# mixer.net
KiCad netlist of a schematic drawn in Altium Designer
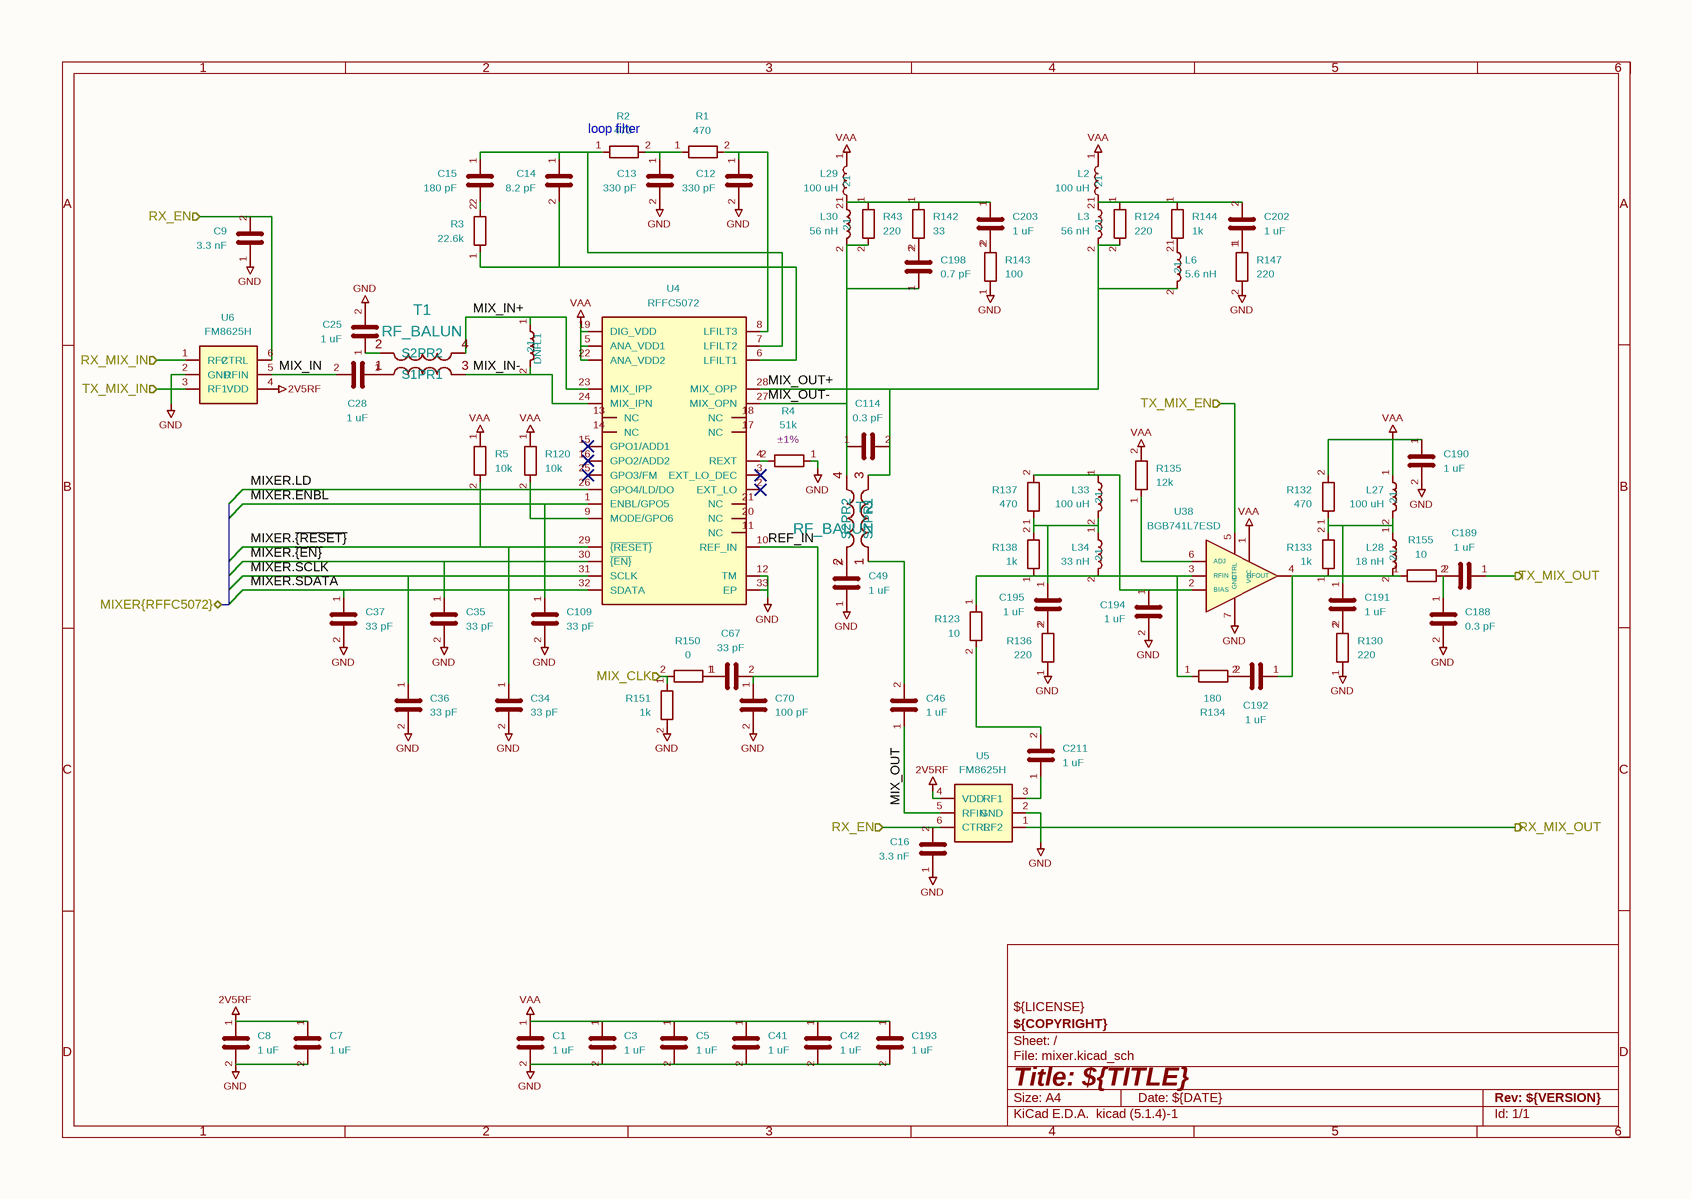
[diagram p0: mixer.SchDoc]

(export (version "E")
  (design (tool "Eeschema 10.0.6"))
  (components
    (comp (ref "C1")
      (value "1 uF")
      (footprint "C_0201_0603Metric")
      (description "CAP CER 1UF 10V X5R 0201")
      (fields (field (name "MANUFACTURER") "Murata") (field (name "PART NUMBER") "GRM033R61A105ME44D"))
      (libsource (lib "Device") (part "C"))
    )
    (comp (ref "C3")
      (value "1 uF")
      (footprint "C_0201_0603Metric")
      (description "CAP CER 1UF 10V X5R 0201")
      (fields (field (name "MANUFACTURER") "Murata") (field (name "PART NUMBER") "GRM033R61A105ME44D"))
      (libsource (lib "Device") (part "C"))
    )
    (comp (ref "C5")
      (value "1 uF")
      (footprint "C_0201_0603Metric")
      (description "CAP CER 1UF 10V X5R 0201")
      (fields (field (name "MANUFACTURER") "Murata") (field (name "PART NUMBER") "GRM033R61A105ME44D"))
      (libsource (lib "Device") (part "C"))
    )
    (comp (ref "C7")
      (value "1 uF")
      (footprint "C_0201_0603Metric")
      (description "CAP CER 1UF 10V X5R 0201")
      (fields (field (name "MANUFACTURER") "Murata") (field (name "PART NUMBER") "GRM033R61A105ME44D"))
      (libsource (lib "Device") (part "C"))
    )
    (comp (ref "C8")
      (value "1 uF")
      (footprint "C_0201_0603Metric")
      (description "CAP CER 1UF 10V X5R 0201")
      (fields (field (name "MANUFACTURER") "Murata") (field (name "PART NUMBER") "GRM033R61A105ME44D"))
      (libsource (lib "Device") (part "C"))
    )
    (comp (ref "C9")
      (value "3.3 nF")
      (footprint "C_0201_0603Metric")
      (description "CAP CER 3300PF 10V X7R 0201")
      (fields (field (name "MANUFACTURER") "Murata") (field (name "PART NUMBER") "GRM033R71A332KA01D"))
      (libsource (lib "Device") (part "C"))
    )
    (comp (ref "C12")
      (value "330 pF")
      (footprint "C_0201_0603Metric")
      (description "CAP CER 330PF 25V C0G/NP0 0201")
      (fields (field (name "MANUFACTURER") "Murata") (field (name "PART NUMBER") "GRM0335C1E331JA01D"))
      (libsource (lib "Device") (part "C"))
    )
    (comp (ref "C13")
      (value "330 pF")
      (footprint "C_0201_0603Metric")
      (description "CAP CER 330PF 25V C0G/NP0 0201")
      (fields (field (name "MANUFACTURER") "Murata") (field (name "PART NUMBER") "GRM0335C1E331JA01D"))
      (libsource (lib "Device") (part "C"))
    )
    (comp (ref "C14")
      (value "8.2 pF")
      (footprint "C_0201_0603Metric")
      (description "CAP CER 8.2PF 50V C0G/NP0 0201")
      (fields (field (name "MANUFACTURER") "Murata") (field (name "PART NUMBER") "GRM0335C1H8R2CA01D"))
      (libsource (lib "Device") (part "C"))
    )
    (comp (ref "C15")
      (value "180 pF")
      (footprint "C_0201_0603Metric")
      (description "CAP CER 180PF 50V C0G/NP0 0201")
      (fields (field (name "MANUFACTURER") "Murata") (field (name "PART NUMBER") "GRM0335C1H181JA01D"))
      (libsource (lib "Device") (part "C"))
    )
    (comp (ref "C16")
      (value "3.3 nF")
      (footprint "C_0201_0603Metric")
      (description "CAP CER 3300PF 10V X7R 0201")
      (fields (field (name "MANUFACTURER") "Murata") (field (name "PART NUMBER") "GRM033R71A332KA01D"))
      (libsource (lib "Device") (part "C"))
    )
    (comp (ref "C25")
      (value "1 uF")
      (footprint "C_0201_0603Metric")
      (description "CAP CER 1UF 10V X5R 0201")
      (fields (field (name "MANUFACTURER") "Murata") (field (name "PART NUMBER") "GRM033R61A105ME44D"))
      (libsource (lib "Device") (part "C"))
    )
    (comp (ref "C28")
      (value "1 uF")
      (footprint "C_0201_0603Metric")
      (description "CAP CER 1UF 10V X5R 0201")
      (fields (field (name "MANUFACTURER") "Murata") (field (name "PART NUMBER") "GRM033R61A105ME44D"))
      (libsource (lib "Device") (part "C"))
    )
    (comp (ref "C34")
      (value "33 pF")
      (footprint "C_0201_0603Metric")
      (description "CAP CER 33PF 50V C0G/NP0 0201")
      (fields (field (name "MANUFACTURER") "Murata") (field (name "PART NUMBER") "GRM0335C1H330JA01D"))
      (libsource (lib "Device") (part "C"))
    )
    (comp (ref "C35")
      (value "33 pF")
      (footprint "C_0201_0603Metric")
      (description "CAP CER 33PF 50V C0G/NP0 0201")
      (fields (field (name "MANUFACTURER") "Murata") (field (name "PART NUMBER") "GRM0335C1H330JA01D"))
      (libsource (lib "Device") (part "C"))
    )
    (comp (ref "C36")
      (value "33 pF")
      (footprint "C_0201_0603Metric")
      (description "CAP CER 33PF 50V C0G/NP0 0201")
      (fields (field (name "MANUFACTURER") "Murata") (field (name "PART NUMBER") "GRM0335C1H330JA01D"))
      (libsource (lib "Device") (part "C"))
    )
    (comp (ref "C37")
      (value "33 pF")
      (footprint "C_0201_0603Metric")
      (description "CAP CER 33PF 50V C0G/NP0 0201")
      (fields (field (name "MANUFACTURER") "Murata") (field (name "PART NUMBER") "GRM0335C1H330JA01D"))
      (libsource (lib "Device") (part "C"))
    )
    (comp (ref "C41")
      (value "1 uF")
      (footprint "C_0201_0603Metric")
      (description "CAP CER 1UF 10V X5R 0201")
      (fields (field (name "MANUFACTURER") "Murata") (field (name "PART NUMBER") "GRM033R61A105ME44D"))
      (libsource (lib "Device") (part "C"))
    )
    (comp (ref "C42")
      (value "1 uF")
      (footprint "C_0201_0603Metric")
      (description "CAP CER 1UF 10V X5R 0201")
      (fields (field (name "MANUFACTURER") "Murata") (field (name "PART NUMBER") "GRM033R61A105ME44D"))
      (libsource (lib "Device") (part "C"))
    )
    (comp (ref "C46")
      (value "1 uF")
      (footprint "C_0201_0603Metric")
      (description "CAP CER 1UF 10V X5R 0201")
      (fields (field (name "MANUFACTURER") "Murata") (field (name "PART NUMBER") "GRM033R61A105ME44D"))
      (libsource (lib "Device") (part "C"))
    )
    (comp (ref "C49")
      (value "1 uF")
      (footprint "C_0201_0603Metric")
      (description "CAP CER 1UF 10V X5R 0201")
      (fields (field (name "MANUFACTURER") "Murata") (field (name "PART NUMBER") "GRM033R61A105ME44D"))
      (libsource (lib "Device") (part "C"))
    )
    (comp (ref "C67")
      (value "33 pF")
      (footprint "C_0201_0603Metric")
      (description "CAP CER 33PF 50V C0G/NP0 0201")
      (fields (field (name "MANUFACTURER") "Murata") (field (name "PART NUMBER") "GRM0335C1H330JA01D"))
      (libsource (lib "Device") (part "C"))
    )
    (comp (ref "C70")
      (value "100 pF")
      (footprint "C_0201_0603Metric")
      (description "CAP CER 100PF 25V C0G/NP0 0201")
      (fields (field (name "MANUFACTURER") "Murata") (field (name "PART NUMBER") "GRM0335C1E101JA01D"))
      (libsource (lib "Device") (part "C"))
    )
    (comp (ref "C109")
      (value "33 pF")
      (footprint "C_0201_0603Metric")
      (description "CAP CER 33PF 50V C0G/NP0 0201")
      (fields (field (name "MANUFACTURER") "Murata") (field (name "PART NUMBER") "GRM0335C1H330JA01D"))
      (libsource (lib "Device") (part "C"))
    )
    (comp (ref "C114")
      (value "0.3 pF")
      (footprint "C_0201_0603Metric")
      (description "CAP CER 0.3PF 25V C0G/NP0 0201")
      (fields (field (name "MANUFACTURER") "Murata") (field (name "PART NUMBER") "GRM0335C1ER30BA01D"))
      (libsource (lib "Device") (part "C"))
    )
    (comp (ref "C188")
      (value "0.3 pF")
      (footprint "C_0201_0603Metric")
      (description "CAP CER 0.3PF 25V C0G/NP0 0201")
      (fields (field (name "MANUFACTURER") "Murata") (field (name "PART NUMBER") "GRM0335C1ER30BA01D"))
      (libsource (lib "Device") (part "C"))
    )
    (comp (ref "C189")
      (value "1 uF")
      (footprint "C_0201_0603Metric")
      (description "CAP CER 1UF 10V X5R 0201")
      (fields (field (name "MANUFACTURER") "Murata") (field (name "PART NUMBER") "GRM033R61A105ME44D"))
      (libsource (lib "Device") (part "C"))
    )
    (comp (ref "C190")
      (value "1 uF")
      (footprint "C_0201_0603Metric")
      (description "CAP CER 1UF 10V X5R 0201")
      (fields (field (name "MANUFACTURER") "Murata") (field (name "PART NUMBER") "GRM033R61A105ME44D"))
      (libsource (lib "Device") (part "C"))
    )
    (comp (ref "C191")
      (value "1 uF")
      (footprint "C_0201_0603Metric")
      (description "CAP CER 1UF 10V X5R 0201")
      (fields (field (name "MANUFACTURER") "Murata") (field (name "PART NUMBER") "GRM033R61A105ME44D"))
      (libsource (lib "Device") (part "C"))
    )
    (comp (ref "C192")
      (value "1 uF")
      (footprint "C_0201_0603Metric")
      (description "CAP CER 1UF 10V X5R 0201")
      (fields (field (name "MANUFACTURER") "Murata") (field (name "PART NUMBER") "GRM033R61A105ME44D"))
      (libsource (lib "Device") (part "C"))
    )
    (comp (ref "C193")
      (value "1 uF")
      (footprint "C_0201_0603Metric")
      (description "CAP CER 1UF 10V X5R 0201")
      (fields (field (name "MANUFACTURER") "Murata") (field (name "PART NUMBER") "GRM033R61A105ME44D"))
      (libsource (lib "Device") (part "C"))
    )
    (comp (ref "C194")
      (value "1 uF")
      (footprint "C_0201_0603Metric")
      (description "CAP CER 1UF 10V X5R 0201")
      (fields (field (name "MANUFACTURER") "Murata") (field (name "PART NUMBER") "GRM033R61A105ME44D"))
      (libsource (lib "Device") (part "C"))
    )
    (comp (ref "C195")
      (value "1 uF")
      (footprint "C_0201_0603Metric")
      (description "CAP CER 1UF 10V X5R 0201")
      (fields (field (name "MANUFACTURER") "Murata") (field (name "PART NUMBER") "GRM033R61A105ME44D"))
      (libsource (lib "Device") (part "C"))
    )
    (comp (ref "C198")
      (value "0.7 pF")
      (footprint "C_0201_0603Metric")
      (description "CAP CER 0.7PF 25V C0G/NP0 0201")
      (fields (field (name "MANUFACTURER") "Murata") (field (name "PART NUMBER") "GRM0335C1ER70WA01D"))
      (libsource (lib "Device") (part "C"))
    )
    (comp (ref "C202")
      (value "1 uF")
      (footprint "C_0201_0603Metric")
      (description "CAP CER 1UF 10V X5R 0201")
      (fields (field (name "MANUFACTURER") "Murata") (field (name "PART NUMBER") "GRM033R61A105ME44D"))
      (libsource (lib "Device") (part "C"))
    )
    (comp (ref "C203")
      (value "1 uF")
      (footprint "C_0201_0603Metric")
      (description "CAP CER 1UF 10V X5R 0201")
      (fields (field (name "MANUFACTURER") "Murata") (field (name "PART NUMBER") "GRM033R61A105ME44D"))
      (libsource (lib "Device") (part "C"))
    )
    (comp (ref "C211")
      (value "1 uF")
      (footprint "C_0201_0603Metric")
      (description "CAP CER 1UF 10V X5R 0201")
      (fields (field (name "MANUFACTURER") "Murata") (field (name "PART NUMBER") "GRM033R61A105ME44D"))
      (libsource (lib "Device") (part "C"))
    )
    (comp (ref "L1") (value "DNP") (footprint "L_0201_0603Metric") (libsource (lib "Device") (part "L")))
    (comp (ref "L2")
      (value "100 uH")
      (footprint "L_TDK_MLZ2012_h1.25mm")
      (description "FIXED IND 100UH 140MA 3.5OHM SMD")
      (fields (field (name "MANUFACTURER") "TDK") (field (name "PART NUMBER") "MLZ2012N101LT000"))
      (libsource (lib "") (part "L_1"))
    )
    (comp (ref "L3")
      (value "56 nH")
      (footprint "L_0201_0603Metric")
      (description "FIXED IND 56NH 100MA 3.9 OHM SMD")
      (fields (field (name "MANUFACTURER") "Murata") (field (name "PART NUMBER") "LQP03TN56NJ02D"))
      (libsource (lib "Device") (part "L"))
    )
    (comp (ref "L6")
      (value "5.6 nH")
      (footprint "L_0201_0603Metric")
      (description "FIXED IND 5.6NH 350MA 400MOHM 0201")
      (fields (field (name "MANUFACTURER") "Murata") (field (name "PART NUMBER") "LQP03TN5N6H02D"))
      (libsource (lib "Device") (part "L"))
    )
    (comp (ref "L27")
      (value "100 uH")
      (footprint "L_TDK_MLZ2012_h1.25mm")
      (description "FIXED IND 100UH 140MA 3.5OHM SMD")
      (fields (field (name "MANUFACTURER") "TDK") (field (name "PART NUMBER") "MLZ2012N101LT000"))
      (libsource (lib "Device") (part "L"))
    )
    (comp (ref "L28")
      (value "18 nH")
      (footprint "L_0201_0603Metric")
      (description "FIXED IND 18NH 200MA 800MOHM SMD")
      (fields (field (name "MANUFACTURER") "Murata") (field (name "PART NUMBER") "LQP03TN18NJ02D"))
      (libsource (lib "Device") (part "L"))
    )
    (comp (ref "L29")
      (value "100 uH")
      (footprint "L_TDK_MLZ2012_h1.25mm")
      (description "FIXED IND 100UH 140MA 3.5OHM SMD")
      (fields (field (name "MANUFACTURER") "TDK") (field (name "PART NUMBER") "MLZ2012N101LT000"))
      (libsource (lib "") (part "L_1"))
    )
    (comp (ref "L30")
      (value "56 nH")
      (footprint "L_0201_0603Metric")
      (description "FIXED IND 56NH 100MA 3.9 OHM SMD")
      (fields (field (name "MANUFACTURER") "Murata") (field (name "PART NUMBER") "LQP03TN56NJ02D"))
      (libsource (lib "Device") (part "L"))
    )
    (comp (ref "L33")
      (value "100 uH")
      (footprint "L_TDK_MLZ2012_h1.25mm")
      (description "FIXED IND 100UH 140MA 3.5OHM SMD")
      (fields (field (name "MANUFACTURER") "TDK") (field (name "PART NUMBER") "MLZ2012N101LT000"))
      (libsource (lib "Device") (part "L"))
    )
    (comp (ref "L34")
      (value "33 nH")
      (footprint "L_0201_0603Metric")
      (description "FIXED IND 33NH 120MA 2.95OHM SMD")
      (fields (field (name "MANUFACTURER") "Murata") (field (name "PART NUMBER") "LQP03TN33NJ02D"))
      (libsource (lib "Device") (part "L"))
    )
    (comp (ref "R1")
      (value "470")
      (footprint "R_0201_0603Metric")
      (description "RES 470 OHM 5% 1/20W 0201")
      (fields (field (name "MANUFACTURER") "Yageo") (field (name "PART NUMBER") "RC0201JR-07470RL"))
      (libsource (lib "") (part "R_3"))
    )
    (comp (ref "R2")
      (value "470")
      (footprint "R_0201_0603Metric")
      (description "RES 470 OHM 5% 1/20W 0201")
      (fields (field (name "MANUFACTURER") "Yageo") (field (name "PART NUMBER") "RC0201JR-07470RL"))
      (libsource (lib "") (part "R_3"))
    )
    (comp (ref "R3")
      (value "22.6k")
      (footprint "R_0201_0603Metric")
      (description "RES 22.6K OHM 1% 1/20W 0201")
      (fields (field (name "MANUFACTURER") "Yageo") (field (name "PART NUMBER") "RC0201FR-0722K6L"))
      (libsource (lib "") (part "R_1"))
    )
    (comp (ref "R4")
      (value "51k")
      (footprint "R_0201_0603Metric")
      (description "RES 51K OHM 1% 1/20W 0201")
      (fields
        (field (name "MANUFACTURER") "Yageo")
        (field (name "PART NUMBER") "RC0201FR-0751KL")
        (field (name "TOLERANCE") "±1%")
      )
      (libsource (lib "") (part "R_2"))
    )
    (comp (ref "R5")
      (value "10k")
      (footprint "R_0402_1005Metric")
      (description "RES 10K OHM 1/16W 5% 0402 SMD")
      (fields (field (name "MANUFACTURER") "Yageo") (field (name "PART NUMBER") "RC0402JR-0710KL"))
      (libsource (lib "Device") (part "R"))
    )
    (comp (ref "R43")
      (value "220")
      (footprint "R_0201_0603Metric")
      (description "RES 220 OHM 5% 1/20W 0201")
      (fields (field (name "MANUFACTURER") "Yageo") (field (name "PART NUMBER") "RC0201JR-07220RL"))
      (libsource (lib "Device") (part "R"))
    )
    (comp (ref "R120")
      (value "10k")
      (footprint "R_0402_1005Metric")
      (description "RES 10K OHM 1/16W 5% 0402 SMD")
      (fields (field (name "MANUFACTURER") "Yageo") (field (name "PART NUMBER") "RC0402JR-0710KL"))
      (libsource (lib "Device") (part "R"))
    )
    (comp (ref "R123")
      (value "10")
      (footprint "R_0201_0603Metric")
      (description "RES 10 OHM 5% 1/20W 0201")
      (fields (field (name "MANUFACTURER") "Yageo") (field (name "PART NUMBER") "RC0201JR-0710RL"))
      (libsource (lib "Device") (part "R"))
    )
    (comp (ref "R124")
      (value "220")
      (footprint "R_0201_0603Metric")
      (description "RES 220 OHM 5% 1/20W 0201")
      (fields (field (name "MANUFACTURER") "Yageo") (field (name "PART NUMBER") "RC0201JR-07220RL"))
      (libsource (lib "Device") (part "R"))
    )
    (comp (ref "R130")
      (value "220")
      (footprint "R_0201_0603Metric")
      (description "RES 220 OHM 5% 1/20W 0201")
      (fields (field (name "MANUFACTURER") "Yageo") (field (name "PART NUMBER") "RC0201JR-07220RL"))
      (libsource (lib "") (part "R_3"))
    )
    (comp (ref "R132")
      (value "470")
      (footprint "R_0201_0603Metric")
      (description "RES 470 OHM 5% 1/20W 0201")
      (fields (field (name "MANUFACTURER") "Yageo") (field (name "PART NUMBER") "RC0201JR-07470RL"))
      (libsource (lib "") (part "R_1"))
    )
    (comp (ref "R133")
      (value "1k")
      (footprint "R_0201_0603Metric")
      (description "RES 1K OHM 1% 1/20W 0201")
      (fields (field (name "MANUFACTURER") "Yageo") (field (name "PART NUMBER") "RC0201FR-071KL"))
      (libsource (lib "") (part "R_1"))
    )
    (comp (ref "R134")
      (value "180")
      (footprint "R_0201_0603Metric")
      (description "RES 180 OHM 5% 1/20W 0201")
      (fields (field (name "MANUFACTURER") "Yageo") (field (name "PART NUMBER") "RC0201JR-07180RL"))
      (libsource (lib "") (part "R_3"))
    )
    (comp (ref "R135")
      (value "12k")
      (footprint "R_0201_0603Metric")
      (description "RES 12K OHM 1% 1/20W 0201")
      (fields (field (name "PART NUMBER") "RC0201FR-0712KL") (field (name "MANUFACTURER") "Yageo"))
      (libsource (lib "") (part "R_3"))
    )
    (comp (ref "R136")
      (value "220")
      (footprint "R_0201_0603Metric")
      (description "RES 220 OHM 5% 1/20W 0201")
      (fields (field (name "MANUFACTURER") "Yageo") (field (name "PART NUMBER") "RC0201JR-07220RL"))
      (libsource (lib "") (part "R_1"))
    )
    (comp (ref "R137")
      (value "470")
      (footprint "R_0201_0603Metric")
      (description "RES 470 OHM 5% 1/20W 0201")
      (fields (field (name "MANUFACTURER") "Yageo") (field (name "PART NUMBER") "RC0201JR-07470RL"))
      (libsource (lib "") (part "R_1"))
    )
    (comp (ref "R138")
      (value "1k")
      (footprint "R_0201_0603Metric")
      (description "RES 1K OHM 1% 1/20W 0201")
      (fields (field (name "MANUFACTURER") "Yageo") (field (name "PART NUMBER") "RC0201FR-071KL"))
      (libsource (lib "") (part "R_1"))
    )
    (comp (ref "R142")
      (value "33")
      (footprint "R_0201_0603Metric")
      (description "RES 33 OHM 5% 1/20W 0201")
      (fields (field (name "MANUFACTURER") "Yageo") (field (name "PART NUMBER") "RC0201JR-0733RL"))
      (libsource (lib "") (part "R_2"))
    )
    (comp (ref "R143")
      (value "100")
      (footprint "R_0201_0603Metric")
      (description "RES 100 OHM 5% 1/20W 0201")
      (fields (field (name "MANUFACTURER") "Yageo") (field (name "PART NUMBER") "RC0201JR-07100RL"))
      (libsource (lib "") (part "R_3"))
    )
    (comp (ref "R144")
      (value "1k")
      (footprint "R_0201_0603Metric")
      (description "RES 1K OHM 1% 1/20W 0201")
      (fields (field (name "MANUFACTURER") "Yageo") (field (name "PART NUMBER") "RC0201FR-071KL"))
      (libsource (lib "") (part "R_2"))
    )
    (comp (ref "R147")
      (value "220")
      (footprint "R_0201_0603Metric")
      (description "RES 220 OHM 5% 1/20W 0201")
      (fields (field (name "MANUFACTURER") "Yageo") (field (name "PART NUMBER") "RC0201JR-07220RL"))
      (libsource (lib "Device") (part "R"))
    )
    (comp (ref "R150")
      (value "0")
      (footprint "R_0201_0603Metric")
      (description "RES 0 OHM JUMPER 1/20W 0201")
      (fields (field (name "MANUFACTURER") "Yageo") (field (name "PART NUMBER") "RC0201JR-070RL"))
      (libsource (lib "Device") (part "R"))
    )
    (comp (ref "R151")
      (value "1k")
      (footprint "R_0201_0603Metric")
      (description "RES 1K OHM 1% 1/20W 0201")
      (fields (field (name "MANUFACTURER") "Yageo") (field (name "PART NUMBER") "RC0201FR-071KL"))
      (libsource (lib "") (part "R_2"))
    )
    (comp (ref "R155")
      (value "10")
      (footprint "R_0201_0603Metric")
      (description "RES 10 OHM 5% 1/20W 0201")
      (fields (field (name "MANUFACTURER") "Yageo") (field (name "PART NUMBER") "RC0201JR-0710RL"))
      (libsource (lib "") (part "R_1"))
    )
    (comp (ref "T1")
      (value "RF_BALUN")
      (footprint "Anaren_0805_2012Metric-6")
      (description "Ultra Low Profile 0805 Balun 50 to 100 ohm Balanced")
      (fields (field (name "MANUFACTURER") "TTM") (field (name "PART NUMBER") "B0310J50100AHF"))
      (libsource (lib "hackrf") (part "BALUN-B0310J50100AHF"))
    )
    (comp (ref "T2")
      (value "RF_BALUN")
      (footprint "Anaren_0805_2012Metric-6")
      (description "Ultra Low Profile 0805 Balun 50 to 100 ohm Balanced")
      (fields (field (name "MANUFACTURER") "TTM") (field (name "PART NUMBER") "B0310J50100AHF"))
      (libsource (lib "hackrf") (part "BALUN-B0310J50100AHF"))
    )
    (comp (ref "U4")
      (value "RFFC5072")
      (footprint "QFN-32-1EP_5x5mm_P0.5mm_EP3.7x3.7mm_ThermalVias")
      (description "WIDEBAND SYNTHESIZER/VCO WITH INTEGRATED 6GHz MIXER")
      (fields (field (name "MANUFACTURER") "RFMD") (field (name "PART NUMBER") "RFFC5072TR7"))
      (libsource (lib "praline") (part "RFFC5072"))
    )
    (comp (ref "U5")
      (value "FM8625H")
      (footprint "TSLP-6-4_1.1x0.7mm_P0.4mm")
      (description "SPDT RF SWITCH")
      (fields (field (name "MANUFACTURER") "Shenzhen Fuman"))
      (libsource (lib "praline") (part "BGS12P2L6"))
    )
    (comp (ref "U6")
      (value "FM8625H")
      (footprint "TSLP-6-4_1.1x0.7mm_P0.4mm")
      (description "SPDT RF SWITCH")
      (fields (field (name "MANUFACTURER") "Shenzhen Fuman"))
      (libsource (lib "") (part "BGS12P2L6_1"))
    )
    (comp (ref "U38")
      (value "BGB741L7ESD")
      (footprint "TSLP-7-1")
      (description "IC AMP CELL 50MHZ-3.5GHZ TSLP7-1")
      (fields (field (name "MANUFACTURER") "Infineon") (field (name "PART NUMBER") "BGB741L7ESDE6327XTSA1"))
      (libsource (lib "praline") (part "BGB741L7ESD"))
    )
  )
  (nets
    (net (code "2") (name "/MIXER.ENBL") (class "Default")
      (node (ref "C109") (pin "1") (pinfunction "1_1") (pintype "passive"))
      (node (ref "U4") (pin "1") (pinfunction "ENBL/GPO5_1") (pintype "passive"))
    )
    (net (code "3") (name "/MIXER.LD") (class "Default")
      (node (ref "U4") (pin "26") (pinfunction "GPO4/LD/DO_26") (pintype "passive"))
    )
    (net (code "4") (name "/MIXER.SCLK") (class "Default")
      (node (ref "C36") (pin "1") (pinfunction "1_1") (pintype "passive"))
      (node (ref "U4") (pin "31") (pinfunction "SCLK_31") (pintype "passive"))
    )
    (net (code "5") (name "/MIXER.SDATA") (class "Default")
      (node (ref "C37") (pin "1") (pinfunction "1_1") (pintype "passive"))
      (node (ref "U4") (pin "32") (pinfunction "SDATA_32") (pintype "passive"))
    )
    (net (code "6") (name "/MIXER.~{{EN}}") (class "Default")
      (node (ref "C35") (pin "1") (pinfunction "1_1") (pintype "passive"))
      (node (ref "U4") (pin "30") (pinfunction "~{{EN}}_30") (pintype "passive"))
    )
    (net (code "7") (name "/MIXER.~{{RESET}}") (class "Default")
      (node (ref "C34") (pin "1") (pinfunction "1_1") (pintype "passive"))
      (node (ref "R5") (pin "2") (pinfunction "2_2") (pintype "passive"))
      (node (ref "U4") (pin "29") (pinfunction "~{{RESET}}_29") (pintype "passive"))
    )
    (net (code "9") (name "/MIX_CLK") (class "Default")
      (node (ref "R150") (pin "2") (pinfunction "2_2") (pintype "passive"))
      (node (ref "R151") (pin "1") (pinfunction "1_1") (pintype "passive"))
    )
    (net (code "10") (name "/MIX_IN") (class "Default")
      (node (ref "C28") (pin "2") (pinfunction "2_2") (pintype "passive"))
      (node (ref "U6") (pin "5") (pinfunction "RFIN_5") (pintype "passive"))
    )
    (net (code "11") (name "/MIX_IN+") (class "Default")
      (node (ref "L1") (pin "1") (pinfunction "1_1") (pintype "passive"))
      (node (ref "T1") (pin "4") (pinfunction "PR2_4") (pintype "passive"))
      (node (ref "U4") (pin "23") (pinfunction "MIX_IPP_23") (pintype "passive"))
    )
    (net (code "12") (name "/MIX_IN-") (class "Default")
      (node (ref "L1") (pin "2") (pinfunction "2_2") (pintype "passive"))
      (node (ref "T1") (pin "3") (pinfunction "PR1_3") (pintype "passive"))
      (node (ref "U4") (pin "24") (pinfunction "MIX_IPN_24") (pintype "passive"))
    )
    (net (code "13") (name "/MIX_OUT") (class "Default")
      (node (ref "C46") (pin "1") (pinfunction "1_1") (pintype "passive"))
      (node (ref "U5") (pin "5") (pinfunction "RFIN_5") (pintype "passive"))
    )
    (net (code "14") (name "/MIX_OUT+") (class "Default")
      (node (ref "C114") (pin "2") (pinfunction "2_2") (pintype "passive"))
      (node (ref "L3") (pin "2") (pinfunction "2_2") (pintype "passive"))
      (node (ref "L6") (pin "2") (pinfunction "2_2") (pintype "passive"))
      (node (ref "R124") (pin "2") (pinfunction "2_2") (pintype "passive"))
      (node (ref "T2") (pin "3") (pinfunction "PR1_3") (pintype "passive"))
      (node (ref "U4") (pin "28") (pinfunction "MIX_OPP_28") (pintype "passive"))
    )
    (net (code "15") (name "/MIX_OUT-") (class "Default")
      (node (ref "C114") (pin "1") (pinfunction "1_1") (pintype "passive"))
      (node (ref "C198") (pin "1") (pinfunction "1_1") (pintype "passive"))
      (node (ref "L30") (pin "2") (pinfunction "2_2") (pintype "passive"))
      (node (ref "R43") (pin "2") (pinfunction "2_2") (pintype "passive"))
      (node (ref "T2") (pin "4") (pinfunction "PR2_4") (pintype "passive"))
      (node (ref "U4") (pin "27") (pinfunction "MIX_OPN_27") (pintype "passive"))
    )
    (net (code "16") (name "/REF_IN") (class "Default")
      (node (ref "C67") (pin "2") (pinfunction "2_2") (pintype "passive"))
      (node (ref "C70") (pin "1") (pinfunction "1_1") (pintype "passive"))
      (node (ref "U4") (pin "10") (pinfunction "REF_IN_10") (pintype "passive"))
    )
    (net (code "17") (name "/RX_EN") (class "Default")
      (node (ref "C16") (pin "2") (pinfunction "2_2") (pintype "passive"))
      (node (ref "C9") (pin "2") (pinfunction "2_2") (pintype "passive"))
      (node (ref "U5") (pin "6") (pinfunction "CTRL_6") (pintype "passive"))
      (node (ref "U6") (pin "6") (pinfunction "CTRL_6") (pintype "passive"))
    )
    (net (code "18") (name "/RX_MIX_IN") (class "Default")
      (node (ref "U6") (pin "1") (pinfunction "RF2_1") (pintype "passive"))
    )
    (net (code "19") (name "/RX_MIX_OUT") (class "Default")
      (node (ref "U5") (pin "1") (pinfunction "RF2_1") (pintype "passive"))
    )
    (net (code "20") (name "/TX_MIX_EN") (class "Default")
      (node (ref "U38") (pin "5") (pinfunction "CTRL_5") (pintype "passive"))
    )
    (net (code "21") (name "/TX_MIX_IN") (class "Default")
      (node (ref "U6") (pin "3") (pinfunction "RF1_3") (pintype "passive"))
    )
    (net (code "22") (name "/TX_MIX_OUT") (class "Default")
      (node (ref "C189") (pin "1") (pinfunction "1_1") (pintype "passive"))
    )
    (net (code "23") (name "2V5RF") (class "Default")
      (node (ref "C7") (pin "1") (pinfunction "1_1") (pintype "passive"))
      (node (ref "C8") (pin "1") (pinfunction "1_1") (pintype "passive"))
      (node (ref "U5") (pin "4") (pinfunction "VDD_4") (pintype "passive"))
      (node (ref "U6") (pin "4") (pinfunction "VDD_4") (pintype "passive"))
    )
    (net (code "24") (name "GND") (class "Default")
      (node (ref "C1") (pin "2") (pinfunction "2_2") (pintype "passive"))
      (node (ref "C109") (pin "2") (pinfunction "2_2") (pintype "passive"))
      (node (ref "C12") (pin "2") (pinfunction "2_2") (pintype "passive"))
      (node (ref "C13") (pin "2") (pinfunction "2_2") (pintype "passive"))
      (node (ref "C16") (pin "1") (pinfunction "1_1") (pintype "passive"))
      (node (ref "C188") (pin "2") (pinfunction "2_2") (pintype "passive"))
      (node (ref "C190") (pin "2") (pinfunction "2_2") (pintype "passive"))
      (node (ref "C193") (pin "2") (pinfunction "2_2") (pintype "passive"))
      (node (ref "C194") (pin "2") (pinfunction "2_2") (pintype "passive"))
      (node (ref "C25") (pin "2") (pinfunction "2_2") (pintype "passive"))
      (node (ref "C3") (pin "2") (pinfunction "2_2") (pintype "passive"))
      (node (ref "C34") (pin "2") (pinfunction "2_2") (pintype "passive"))
      (node (ref "C35") (pin "2") (pinfunction "2_2") (pintype "passive"))
      (node (ref "C36") (pin "2") (pinfunction "2_2") (pintype "passive"))
      (node (ref "C37") (pin "2") (pinfunction "2_2") (pintype "passive"))
      (node (ref "C41") (pin "2") (pinfunction "2_2") (pintype "passive"))
      (node (ref "C42") (pin "2") (pinfunction "2_2") (pintype "passive"))
      (node (ref "C49") (pin "1") (pinfunction "1_1") (pintype "passive"))
      (node (ref "C5") (pin "2") (pinfunction "2_2") (pintype "passive"))
      (node (ref "C7") (pin "2") (pinfunction "2_2") (pintype "passive"))
      (node (ref "C70") (pin "2") (pinfunction "2_2") (pintype "passive"))
      (node (ref "C8") (pin "2") (pinfunction "2_2") (pintype "passive"))
      (node (ref "C9") (pin "1") (pinfunction "1_1") (pintype "passive"))
      (node (ref "R130") (pin "1") (pinfunction "1_1") (pintype "passive"))
      (node (ref "R136") (pin "1") (pinfunction "1_1") (pintype "passive"))
      (node (ref "R143") (pin "1") (pinfunction "1_1") (pintype "passive"))
      (node (ref "R147") (pin "2") (pinfunction "2_2") (pintype "passive"))
      (node (ref "R151") (pin "2") (pinfunction "2_2") (pintype "passive"))
      (node (ref "R4") (pin "1") (pinfunction "1_1") (pintype "passive"))
      (node (ref "U38") (pin "7") (pinfunction "GND_7") (pintype "passive"))
      (node (ref "U4") (pin "12") (pinfunction "TM_12") (pintype "passive"))
      (node (ref "U4") (pin "33") (pinfunction "EP_33") (pintype "passive"))
      (node (ref "U5") (pin "2") (pinfunction "GND_2") (pintype "passive"))
      (node (ref "U6") (pin "2") (pinfunction "GND_2") (pintype "passive"))
    )
    (net (code "25") (name "Net-(C13-Pad1)") (class "Default")
      (node (ref "C13") (pin "1") (pinfunction "1_1") (pintype "passive"))
      (node (ref "R1") (pin "1") (pinfunction "1_1") (pintype "passive"))
      (node (ref "R2") (pin "2") (pinfunction "2_2") (pintype "passive"))
    )
    (net (code "26") (name "Net-(C15-Pad2)") (class "Default")
      (node (ref "C15") (pin "2") (pinfunction "2_2") (pintype "passive"))
      (node (ref "R3") (pin "2") (pinfunction "2_2") (pintype "passive"))
    )
    (net (code "27") (name "Net-(C67-Pad1)") (class "Default")
      (node (ref "C67") (pin "1") (pinfunction "1_1") (pintype "passive"))
      (node (ref "R150") (pin "1") (pinfunction "1_1") (pintype "passive"))
    )
    (net (code "28") (name "Net-(C188-Pad1)") (class "Default")
      (node (ref "C188") (pin "1") (pinfunction "1_1") (pintype "passive"))
      (node (ref "C189") (pin "2") (pinfunction "2_2") (pintype "passive"))
      (node (ref "R155") (pin "2") (pinfunction "2_2") (pintype "passive"))
    )
    (net (code "29") (name "Net-(C191-Pad1)") (class "Default")
      (node (ref "C191") (pin "1") (pinfunction "1_1") (pintype "passive"))
      (node (ref "L27") (pin "2") (pinfunction "2_2") (pintype "passive"))
      (node (ref "L28") (pin "1") (pinfunction "1_1") (pintype "passive"))
      (node (ref "R132") (pin "1") (pinfunction "1_1") (pintype "passive"))
      (node (ref "R133") (pin "2") (pinfunction "2_2") (pintype "passive"))
    )
    (net (code "30") (name "Net-(C191-Pad2)") (class "Default")
      (node (ref "C191") (pin "2") (pinfunction "2_2") (pintype "passive"))
      (node (ref "R130") (pin "2") (pinfunction "2_2") (pintype "passive"))
    )
    (net (code "31") (name "Net-(C192-Pad2)") (class "Default")
      (node (ref "C192") (pin "2") (pinfunction "2_2") (pintype "passive"))
      (node (ref "R134") (pin "2") (pinfunction "2_2") (pintype "passive"))
    )
    (net (code "32") (name "Net-(C195-Pad1)") (class "Default")
      (node (ref "C195") (pin "1") (pinfunction "1_1") (pintype "passive"))
      (node (ref "L33") (pin "2") (pinfunction "2_2") (pintype "passive"))
      (node (ref "L34") (pin "1") (pinfunction "1_1") (pintype "passive"))
      (node (ref "R137") (pin "1") (pinfunction "1_1") (pintype "passive"))
      (node (ref "R138") (pin "2") (pinfunction "2_2") (pintype "passive"))
    )
    (net (code "33") (name "Net-(C195-Pad2)") (class "Default")
      (node (ref "C195") (pin "2") (pinfunction "2_2") (pintype "passive"))
      (node (ref "R136") (pin "2") (pinfunction "2_2") (pintype "passive"))
    )
    (net (code "34") (name "Net-(C198-Pad2)") (class "Default")
      (node (ref "C198") (pin "2") (pinfunction "2_2") (pintype "passive"))
      (node (ref "R142") (pin "2") (pinfunction "2_2") (pintype "passive"))
    )
    (net (code "35") (name "Net-(C202-Pad1)") (class "Default")
      (node (ref "C202") (pin "1") (pinfunction "1_1") (pintype "passive"))
      (node (ref "R147") (pin "1") (pinfunction "1_1") (pintype "passive"))
    )
    (net (code "36") (name "Net-(C202-Pad2)") (class "Default")
      (node (ref "C202") (pin "2") (pinfunction "2_2") (pintype "passive"))
      (node (ref "L2") (pin "2") (pinfunction "2_2") (pintype "passive"))
      (node (ref "L3") (pin "1") (pinfunction "1_1") (pintype "passive"))
      (node (ref "R124") (pin "1") (pinfunction "1_1") (pintype "passive"))
      (node (ref "R144") (pin "1") (pinfunction "1_1") (pintype "passive"))
    )
    (net (code "37") (name "Net-(C203-Pad1)") (class "Default")
      (node (ref "C203") (pin "1") (pinfunction "1_1") (pintype "passive"))
      (node (ref "L29") (pin "2") (pinfunction "2_2") (pintype "passive"))
      (node (ref "L30") (pin "1") (pinfunction "1_1") (pintype "passive"))
      (node (ref "R142") (pin "1") (pinfunction "1_1") (pintype "passive"))
      (node (ref "R43") (pin "1") (pinfunction "1_1") (pintype "passive"))
    )
    (net (code "38") (name "Net-(C203-Pad2)") (class "Default")
      (node (ref "C203") (pin "2") (pinfunction "2_2") (pintype "passive"))
      (node (ref "R143") (pin "2") (pinfunction "2_2") (pintype "passive"))
    )
    (net (code "39") (name "Net-(C211-Pad2)") (class "Default")
      (node (ref "C211") (pin "2") (pinfunction "2_2") (pintype "passive"))
      (node (ref "R123") (pin "2") (pinfunction "2_2") (pintype "passive"))
    )
    (net (code "40") (name "Net-(L6-Pad1)") (class "Default")
      (node (ref "L6") (pin "1") (pinfunction "1_1") (pintype "passive"))
      (node (ref "R144") (pin "2") (pinfunction "2_2") (pintype "passive"))
    )
    (net (code "41") (name "Net-(T1-S1)") (class "Default")
      (node (ref "C28") (pin "1") (pinfunction "1_1") (pintype "passive"))
      (node (ref "T1") (pin "1") (pinfunction "S1_1") (pintype "passive"))
    )
    (net (code "42") (name "Net-(T1-S2)") (class "Default")
      (node (ref "C25") (pin "1") (pinfunction "1_1") (pintype "passive"))
      (node (ref "T1") (pin "2") (pinfunction "S2_2") (pintype "passive"))
    )
    (net (code "43") (name "Net-(T2-S1)") (class "Default")
      (node (ref "C46") (pin "2") (pinfunction "2_2") (pintype "passive"))
      (node (ref "T2") (pin "1") (pinfunction "S1_1") (pintype "passive"))
    )
    (net (code "44") (name "Net-(T2-S2)") (class "Default")
      (node (ref "C49") (pin "2") (pinfunction "2_2") (pintype "passive"))
      (node (ref "T2") (pin "2") (pinfunction "S2_2") (pintype "passive"))
    )
    (net (code "45") (name "Net-(U4-LFILT1)") (class "Default")
      (node (ref "C14") (pin "2") (pinfunction "2_2") (pintype "passive"))
      (node (ref "R3") (pin "1") (pinfunction "1_1") (pintype "passive"))
      (node (ref "U4") (pin "6") (pinfunction "LFILT1_6") (pintype "passive"))
    )
    (net (code "46") (name "Net-(U4-LFILT2)") (class "Default")
      (node (ref "C14") (pin "1") (pinfunction "1_1") (pintype "passive"))
      (node (ref "C15") (pin "1") (pinfunction "1_1") (pintype "passive"))
      (node (ref "R2") (pin "1") (pinfunction "1_1") (pintype "passive"))
      (node (ref "U4") (pin "7") (pinfunction "LFILT2_7") (pintype "passive"))
    )
    (net (code "47") (name "Net-(U4-LFILT3)") (class "Default")
      (node (ref "C12") (pin "1") (pinfunction "1_1") (pintype "passive"))
      (node (ref "R1") (pin "2") (pinfunction "2_2") (pintype "passive"))
      (node (ref "U4") (pin "8") (pinfunction "LFILT3_8") (pintype "passive"))
    )
    (net (code "48") (name "Net-(U4-MODE{slash}GPO6)") (class "Default")
      (node (ref "R120") (pin "2") (pinfunction "2_2") (pintype "passive"))
      (node (ref "U4") (pin "9") (pinfunction "MODE/GPO6_9") (pintype "passive"))
    )
    (net (code "49") (name "Net-(U4-REXT)") (class "Default")
      (node (ref "R4") (pin "2") (pinfunction "2_2") (pintype "passive"))
      (node (ref "U4") (pin "4") (pinfunction "REXT_4") (pintype "passive"))
    )
    (net (code "50") (name "Net-(U5-RF1)") (class "Default")
      (node (ref "C211") (pin "1") (pinfunction "1_1") (pintype "passive"))
      (node (ref "U5") (pin "3") (pinfunction "RF1_3") (pintype "passive"))
    )
    (net (code "51") (name "Net-(U38-ADJ)") (class "Default")
      (node (ref "R135") (pin "1") (pinfunction "1_1") (pintype "passive"))
      (node (ref "U38") (pin "6") (pinfunction "ADJ_6") (pintype "passive"))
    )
    (net (code "52") (name "Net-(U38-BIAS)") (class "Default")
      (node (ref "C194") (pin "1") (pinfunction "1_1") (pintype "passive"))
      (node (ref "L33") (pin "1") (pinfunction "1_1") (pintype "passive"))
      (node (ref "R137") (pin "2") (pinfunction "2_2") (pintype "passive"))
      (node (ref "U38") (pin "2") (pinfunction "BIAS_2") (pintype "passive"))
    )
    (net (code "53") (name "Net-(U38-RFIN)") (class "Default")
      (node (ref "L34") (pin "2") (pinfunction "2_2") (pintype "passive"))
      (node (ref "R123") (pin "1") (pinfunction "1_1") (pintype "passive"))
      (node (ref "R134") (pin "1") (pinfunction "1_1") (pintype "passive"))
      (node (ref "R138") (pin "1") (pinfunction "1_1") (pintype "passive"))
      (node (ref "U38") (pin "3") (pinfunction "RFIN_3") (pintype "passive"))
    )
    (net (code "54") (name "Net-(U38-RFOUT)") (class "Default")
      (node (ref "C192") (pin "1") (pinfunction "1_1") (pintype "passive"))
      (node (ref "L28") (pin "2") (pinfunction "2_2") (pintype "passive"))
      (node (ref "R133") (pin "1") (pinfunction "1_1") (pintype "passive"))
      (node (ref "R155") (pin "1") (pinfunction "1_1") (pintype "passive"))
      (node (ref "U38") (pin "4") (pinfunction "RFOUT_4") (pintype "passive"))
    )
    (net (code "55") (name "VAA") (class "Default")
      (node (ref "C1") (pin "1") (pinfunction "1_1") (pintype "passive"))
      (node (ref "C190") (pin "1") (pinfunction "1_1") (pintype "passive"))
      (node (ref "C193") (pin "1") (pinfunction "1_1") (pintype "passive"))
      (node (ref "C3") (pin "1") (pinfunction "1_1") (pintype "passive"))
      (node (ref "C41") (pin "1") (pinfunction "1_1") (pintype "passive"))
      (node (ref "C42") (pin "1") (pinfunction "1_1") (pintype "passive"))
      (node (ref "C5") (pin "1") (pinfunction "1_1") (pintype "passive"))
      (node (ref "L2") (pin "1") (pinfunction "1_1") (pintype "passive"))
      (node (ref "L27") (pin "1") (pinfunction "1_1") (pintype "passive"))
      (node (ref "L29") (pin "1") (pinfunction "1_1") (pintype "passive"))
      (node (ref "R120") (pin "1") (pinfunction "1_1") (pintype "passive"))
      (node (ref "R132") (pin "2") (pinfunction "2_2") (pintype "passive"))
      (node (ref "R135") (pin "2") (pinfunction "2_2") (pintype "passive"))
      (node (ref "R5") (pin "1") (pinfunction "1_1") (pintype "passive"))
      (node (ref "U38") (pin "1") (pinfunction "VCC_1") (pintype "passive"))
      (node (ref "U4") (pin "19") (pinfunction "DIG_VDD_19") (pintype "passive"))
      (node (ref "U4") (pin "22") (pinfunction "ANA_VDD2_22") (pintype "passive"))
      (node (ref "U4") (pin "5") (pinfunction "ANA_VDD1_5") (pintype "passive"))
    )
    (net (code "56") (name "unconnected-(U4-EXT_LO-Pad2)") (class "Default")
      (node (ref "U4") (pin "2") (pinfunction "EXT_LO_2") (pintype "passive+no_connect"))
    )
    (net (code "57") (name "unconnected-(U4-EXT_LO_DEC-Pad3)") (class "Default")
      (node (ref "U4") (pin "3") (pinfunction "EXT_LO_DEC_3") (pintype "passive+no_connect"))
    )
    (net (code "58") (name "unconnected-(U4-GPO1{slash}ADD1-Pad15)") (class "Default")
      (node (ref "U4") (pin "15") (pinfunction "GPO1/ADD1_15") (pintype "passive+no_connect"))
    )
    (net (code "59") (name "unconnected-(U4-GPO2{slash}ADD2-Pad16)") (class "Default")
      (node (ref "U4") (pin "16") (pinfunction "GPO2/ADD2_16") (pintype "passive+no_connect"))
    )
    (net (code "60") (name "unconnected-(U4-GPO3{slash}FM-Pad25)") (class "Default")
      (node (ref "U4") (pin "25") (pinfunction "GPO3/FM_25") (pintype "passive+no_connect"))
    )
    (net (code "61") (name "unconnected-(U4-NC-Pad11)") (class "Default")
      (node (ref "U4") (pin "11") (pinfunction "NC_11") (pintype "passive"))
    )
    (net (code "62") (name "unconnected-(U4-NC-Pad13)") (class "Default")
      (node (ref "U4") (pin "13") (pinfunction "NC_13") (pintype "passive"))
    )
    (net (code "63") (name "unconnected-(U4-NC-Pad14)") (class "Default")
      (node (ref "U4") (pin "14") (pinfunction "NC_14") (pintype "passive"))
    )
    (net (code "64") (name "unconnected-(U4-NC-Pad17)") (class "Default")
      (node (ref "U4") (pin "17") (pinfunction "NC_17") (pintype "passive"))
    )
    (net (code "65") (name "unconnected-(U4-NC-Pad18)") (class "Default")
      (node (ref "U4") (pin "18") (pinfunction "NC_18") (pintype "passive"))
    )
    (net (code "66") (name "unconnected-(U4-NC-Pad20)") (class "Default")
      (node (ref "U4") (pin "20") (pinfunction "NC_20") (pintype "passive"))
    )
    (net (code "67") (name "unconnected-(U4-NC-Pad21)") (class "Default")
      (node (ref "U4") (pin "21") (pinfunction "NC_21") (pintype "passive"))
    )
  )
)
